# Power_1.net
KiCad netlist of a schematic drawn in Altium Designer
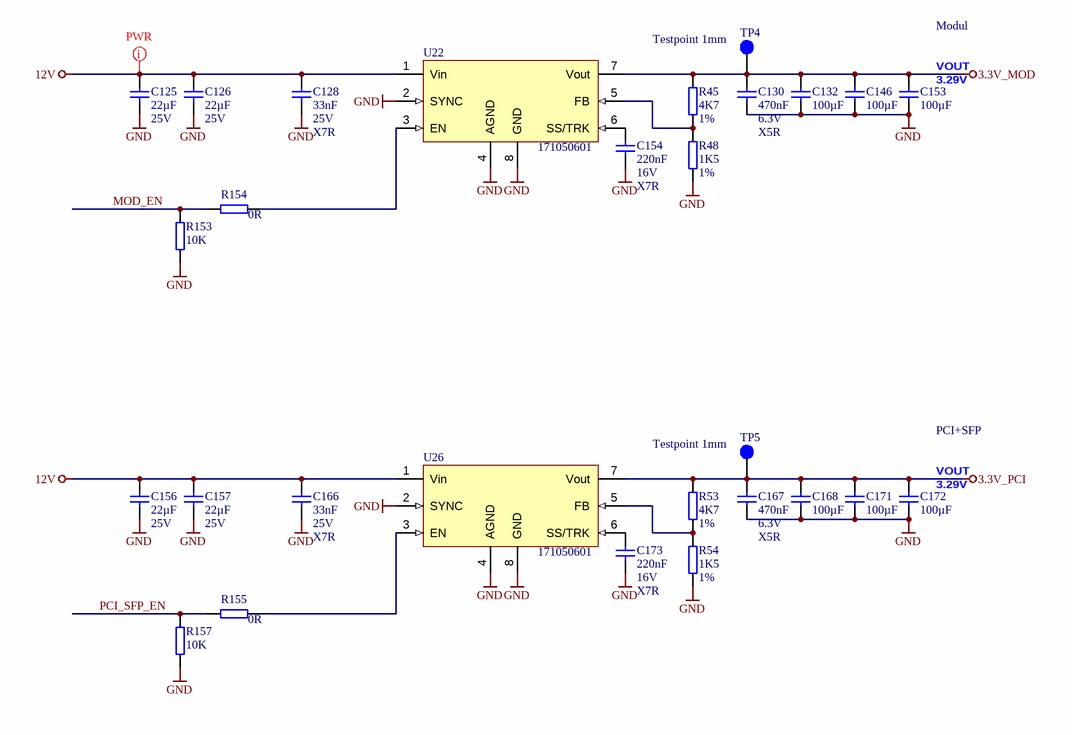
[diagram p0: Power_1.schdoc]

(export (version "E")
  (design (tool "Eeschema 10.0.6"))
  (components
    (comp (ref "C125")
      (value "22µF")
      (footprint "CAPC3216X180N")
      (description "KON 22µF X5R 25V SMD 10%")
      (fields (field (name "VOLTAGE") "25V") (field (name "TOLERANCE") "10%"))
      (libsource (lib "TE") (part "CAP-NP"))
    )
    (comp (ref "C126")
      (value "22µF")
      (footprint "CAPC3216X180N")
      (description "KON 22µF X5R 25V SMD 10%")
      (fields (field (name "VOLTAGE") "25V") (field (name "TOLERANCE") "10%"))
      (libsource (lib "TE") (part "CAP-NP"))
    )
    (comp (ref "C128")
      (value "33nF")
      (footprint "CAPC1005X55N")
      (description "KON 33nF 25V X7R SMD")
      (fields (field (name "VOLTAGE") "25V") (field (name "TECHNOLOGY") "X7R"))
      (libsource (lib "TE") (part "CAP-NP"))
    )
    (comp (ref "C130")
      (value "470nF")
      (footprint "CAPC1005X55N")
      (description "KON 470nF 6,3V X5R SMD")
      (fields (field (name "VOLTAGE") "6.3V") (field (name "TECHNOLOGY") "X5R"))
      (libsource (lib "TE") (part "CAP-NP"))
    )
    (comp (ref "C132")
      (value "100µF")
      (footprint "CAPC3216X180N")
      (description "KON 100µF 6,3V X5R SMD 20%")
      (fields (field (name "TOLERANCE") "20%") (field (name "VOLTAGE") "6.3V"))
      (libsource (lib "TE") (part "CAP-NP"))
    )
    (comp (ref "C146")
      (value "100µF")
      (footprint "CAPC3216X180N")
      (description "KON 100µF 6,3V X5R SMD 20%")
      (fields (field (name "TOLERANCE") "20%") (field (name "VOLTAGE") "6.3V"))
      (libsource (lib "TE") (part "CAP-NP"))
    )
    (comp (ref "C153")
      (value "100µF")
      (footprint "CAPC3216X180N")
      (description "KON 100µF 6,3V X5R SMD 20%")
      (fields (field (name "TOLERANCE") "20%") (field (name "VOLTAGE") "6.3V"))
      (libsource (lib "TE") (part "CAP-NP"))
    )
    (comp (ref "C154")
      (value "220nF")
      (footprint "CAPC1005X55N")
      (description "KON 220nF 16V X7R SMD")
      (fields (field (name "VOLTAGE") "16V") (field (name "TECHNOLOGY") "X7R"))
      (libsource (lib "TE") (part "CAP-NP"))
    )
    (comp (ref "C156")
      (value "22µF")
      (footprint "CAPC3216X180N")
      (description "KON 22µF X5R 25V SMD 10%")
      (fields (field (name "VOLTAGE") "25V") (field (name "TOLERANCE") "10%"))
      (libsource (lib "TE") (part "CAP-NP"))
    )
    (comp (ref "C157")
      (value "22µF")
      (footprint "CAPC3216X180N")
      (description "KON 22µF X5R 25V SMD 10%")
      (fields (field (name "VOLTAGE") "25V") (field (name "TOLERANCE") "10%"))
      (libsource (lib "TE") (part "CAP-NP"))
    )
    (comp (ref "C166")
      (value "33nF")
      (footprint "CAPC1005X55N")
      (description "KON 33nF 25V X7R SMD")
      (fields (field (name "VOLTAGE") "25V") (field (name "TECHNOLOGY") "X7R"))
      (libsource (lib "TE") (part "CAP-NP"))
    )
    (comp (ref "C167")
      (value "470nF")
      (footprint "CAPC1005X55N")
      (description "KON 470nF 6,3V X5R SMD")
      (fields (field (name "VOLTAGE") "6.3V") (field (name "TECHNOLOGY") "X5R"))
      (libsource (lib "TE") (part "CAP-NP"))
    )
    (comp (ref "C168")
      (value "100µF")
      (footprint "CAPC3216X180N")
      (description "KON 100µF 6,3V X5R SMD 20%")
      (fields (field (name "TOLERANCE") "20%") (field (name "VOLTAGE") "6.3V"))
      (libsource (lib "TE") (part "CAP-NP"))
    )
    (comp (ref "C171")
      (value "100µF")
      (footprint "CAPC3216X180N")
      (description "KON 100µF 6,3V X5R SMD 20%")
      (fields (field (name "TOLERANCE") "20%") (field (name "VOLTAGE") "6.3V"))
      (libsource (lib "TE") (part "CAP-NP"))
    )
    (comp (ref "C172")
      (value "100µF")
      (footprint "CAPC3216X180N")
      (description "KON 100µF 6,3V X5R SMD 20%")
      (fields (field (name "TOLERANCE") "20%") (field (name "VOLTAGE") "6.3V"))
      (libsource (lib "TE") (part "CAP-NP"))
    )
    (comp (ref "C173")
      (value "220nF")
      (footprint "CAPC1005X55N")
      (description "KON 220nF 16V X7R SMD")
      (fields (field (name "VOLTAGE") "16V") (field (name "TECHNOLOGY") "X7R"))
      (libsource (lib "TE") (part "CAP-NP"))
    )
    (comp (ref "R45")
      (value "4K7")
      (footprint "RESC1005X40N")
      (description "WID SMD 4K7 1% 0,063W")
      (fields (field (name "TOLERANCE") "1%"))
      (libsource (lib "TE") (part "RES"))
    )
    (comp (ref "R48")
      (value "1K5")
      (footprint "RESC1005X40N")
      (description "WID SMD 1K5 1% 0,063W")
      (fields (field (name "TOLERANCE") "1%"))
      (libsource (lib "TE") (part "RES"))
    )
    (comp (ref "R53")
      (value "4K7")
      (footprint "RESC1005X40N")
      (description "WID SMD 4K7 1% 0,063W")
      (fields (field (name "TOLERANCE") "1%"))
      (libsource (lib "TE") (part "RES"))
    )
    (comp (ref "R54")
      (value "1K5")
      (footprint "RESC1005X40N")
      (description "WID SMD 1K5 1% 0,063W")
      (fields (field (name "TOLERANCE") "1%"))
      (libsource (lib "TE") (part "RES"))
    )
    (comp (ref "R153")
      (value "10K")
      (footprint "RESC1005X40N")
      (description "WID SMD 10K 1% 0,063W")
      (fields (field (name "TOLERANCE") "1%"))
      (libsource (lib "TE") (part "RES"))
    )
    (comp (ref "R154")
      (value "0R")
      (footprint "RESC1005X40N")
      (description "WID SMD 0R")
      (fields (field (name "TOLERANCE") "1%"))
      (libsource (lib "TE") (part "RES"))
    )
    (comp (ref "R155")
      (value "0R")
      (footprint "RESC1005X40N")
      (description "WID SMD 0R")
      (fields (field (name "TOLERANCE") "1%"))
      (libsource (lib "TE") (part "RES"))
    )
    (comp (ref "R157")
      (value "10K")
      (footprint "RESC1005X40N")
      (description "WID SMD 10K 1% 0,063W")
      (fields (field (name "TOLERANCE") "1%"))
      (libsource (lib "TE") (part "RES"))
    )
    (comp (ref "TP4") (value "Testpoint 1mm") (footprint "TP_1mm") (libsource (lib "TE") (part "TP")))
    (comp (ref "TP5") (value "Testpoint 1mm") (footprint "TP_1mm") (libsource (lib "TE") (part "TP")))
    (comp (ref "U22")
      (value "171050601")
      (footprint "7TO-PMOD")
      (libsource (lib "TE") (part "WE-DCDC-171050601"))
    )
    (comp (ref "U26")
      (value "171050601")
      (footprint "7TO-PMOD")
      (libsource (lib "TE") (part "WE-DCDC-171050601"))
    )
  )
  (nets
    (net (code "1") (name "/MOD_EN") (class "Default")
      (node (ref "R153") (pin "2") (pinfunction "2_2") (pintype "passive"))
      (node (ref "R154") (pin "2") (pinfunction "2_2") (pintype "passive"))
    )
    (net (code "2") (name "/PCI_SFP_EN") (class "Default")
      (node (ref "R155") (pin "2") (pinfunction "2_2") (pintype "passive"))
      (node (ref "R157") (pin "2") (pinfunction "2_2") (pintype "passive"))
    )
    (net (code "3") (name "3.3V_MOD") (class "Default")
      (node (ref "C130") (pin "1") (pinfunction "1_1") (pintype "passive"))
      (node (ref "C132") (pin "1") (pinfunction "1_1") (pintype "passive"))
      (node (ref "C146") (pin "1") (pinfunction "1_1") (pintype "passive"))
      (node (ref "C153") (pin "1") (pinfunction "1_1") (pintype "passive"))
      (node (ref "R45") (pin "1") (pinfunction "1_1") (pintype "passive"))
      (node (ref "TP4") (pin "1") (pintype "passive"))
      (node (ref "U22") (pin "7") (pinfunction "Vout_7") (pintype "power_in"))
    )
    (net (code "4") (name "3.3V_PCI") (class "Default")
      (node (ref "C167") (pin "1") (pinfunction "1_1") (pintype "passive"))
      (node (ref "C168") (pin "1") (pinfunction "1_1") (pintype "passive"))
      (node (ref "C171") (pin "1") (pinfunction "1_1") (pintype "passive"))
      (node (ref "C172") (pin "1") (pinfunction "1_1") (pintype "passive"))
      (node (ref "R53") (pin "1") (pinfunction "1_1") (pintype "passive"))
      (node (ref "TP5") (pin "1") (pintype "passive"))
      (node (ref "U26") (pin "7") (pinfunction "Vout_7") (pintype "power_in"))
    )
    (net (code "5") (name "12V") (class "Default")
      (node (ref "C125") (pin "2") (pinfunction "2_2") (pintype "passive"))
      (node (ref "C126") (pin "2") (pinfunction "2_2") (pintype "passive"))
      (node (ref "C128") (pin "1") (pinfunction "1_1") (pintype "passive"))
      (node (ref "C156") (pin "2") (pinfunction "2_2") (pintype "passive"))
      (node (ref "C157") (pin "2") (pinfunction "2_2") (pintype "passive"))
      (node (ref "C166") (pin "1") (pinfunction "1_1") (pintype "passive"))
      (node (ref "U22") (pin "1") (pinfunction "Vin_1") (pintype "power_in"))
      (node (ref "U26") (pin "1") (pinfunction "Vin_1") (pintype "power_in"))
    )
    (net (code "6") (name "GND") (class "Default")
      (node (ref "C125") (pin "1") (pinfunction "1_1") (pintype "passive"))
      (node (ref "C126") (pin "1") (pinfunction "1_1") (pintype "passive"))
      (node (ref "C128") (pin "2") (pinfunction "2_2") (pintype "passive"))
      (node (ref "C130") (pin "2") (pinfunction "2_2") (pintype "passive"))
      (node (ref "C132") (pin "2") (pinfunction "2_2") (pintype "passive"))
      (node (ref "C146") (pin "2") (pinfunction "2_2") (pintype "passive"))
      (node (ref "C153") (pin "2") (pinfunction "2_2") (pintype "passive"))
      (node (ref "C154") (pin "2") (pinfunction "2_2") (pintype "passive"))
      (node (ref "C156") (pin "1") (pinfunction "1_1") (pintype "passive"))
      (node (ref "C157") (pin "1") (pinfunction "1_1") (pintype "passive"))
      (node (ref "C166") (pin "2") (pinfunction "2_2") (pintype "passive"))
      (node (ref "C167") (pin "2") (pinfunction "2_2") (pintype "passive"))
      (node (ref "C168") (pin "2") (pinfunction "2_2") (pintype "passive"))
      (node (ref "C171") (pin "2") (pinfunction "2_2") (pintype "passive"))
      (node (ref "C172") (pin "2") (pinfunction "2_2") (pintype "passive"))
      (node (ref "C173") (pin "2") (pinfunction "2_2") (pintype "passive"))
      (node (ref "R153") (pin "1") (pinfunction "1_1") (pintype "passive"))
      (node (ref "R157") (pin "1") (pinfunction "1_1") (pintype "passive"))
      (node (ref "R48") (pin "2") (pinfunction "2_2") (pintype "passive"))
      (node (ref "R54") (pin "2") (pinfunction "2_2") (pintype "passive"))
      (node (ref "U22") (pin "2") (pinfunction "SYNC_2") (pintype "input"))
      (node (ref "U22") (pin "4") (pinfunction "AGND_4") (pintype "power_in"))
      (node (ref "U22") (pin "8") (pinfunction "GND_8") (pintype "power_in"))
      (node (ref "U26") (pin "2") (pinfunction "SYNC_2") (pintype "input"))
      (node (ref "U26") (pin "4") (pinfunction "AGND_4") (pintype "power_in"))
      (node (ref "U26") (pin "8") (pinfunction "GND_8") (pintype "power_in"))
    )
    (net (code "7") (name "Net-(U22-EN)") (class "Default")
      (node (ref "R154") (pin "1") (pinfunction "1_1") (pintype "passive"))
      (node (ref "U22") (pin "3") (pinfunction "EN_3") (pintype "input"))
    )
    (net (code "8") (name "Net-(U22-FB)") (class "Default")
      (node (ref "R45") (pin "2") (pinfunction "2_2") (pintype "passive"))
      (node (ref "R48") (pin "1") (pinfunction "1_1") (pintype "passive"))
      (node (ref "U22") (pin "5") (pinfunction "FB_5") (pintype "input"))
    )
    (net (code "9") (name "Net-(U22-SS{slash}TRK)") (class "Default")
      (node (ref "C154") (pin "1") (pinfunction "1_1") (pintype "passive"))
      (node (ref "U22") (pin "6") (pinfunction "SS/TRK_6") (pintype "input"))
    )
    (net (code "10") (name "Net-(U26-EN)") (class "Default")
      (node (ref "R155") (pin "1") (pinfunction "1_1") (pintype "passive"))
      (node (ref "U26") (pin "3") (pinfunction "EN_3") (pintype "input"))
    )
    (net (code "11") (name "Net-(U26-FB)") (class "Default")
      (node (ref "R53") (pin "2") (pinfunction "2_2") (pintype "passive"))
      (node (ref "R54") (pin "1") (pinfunction "1_1") (pintype "passive"))
      (node (ref "U26") (pin "5") (pinfunction "FB_5") (pintype "input"))
    )
    (net (code "12") (name "Net-(U26-SS{slash}TRK)") (class "Default")
      (node (ref "C173") (pin "1") (pinfunction "1_1") (pintype "passive"))
      (node (ref "U26") (pin "6") (pinfunction "SS/TRK_6") (pintype "input"))
    )
  )
)
